# seedrum_triac_v1.net
KiCad netlist of a schematic drawn in EasyEDA
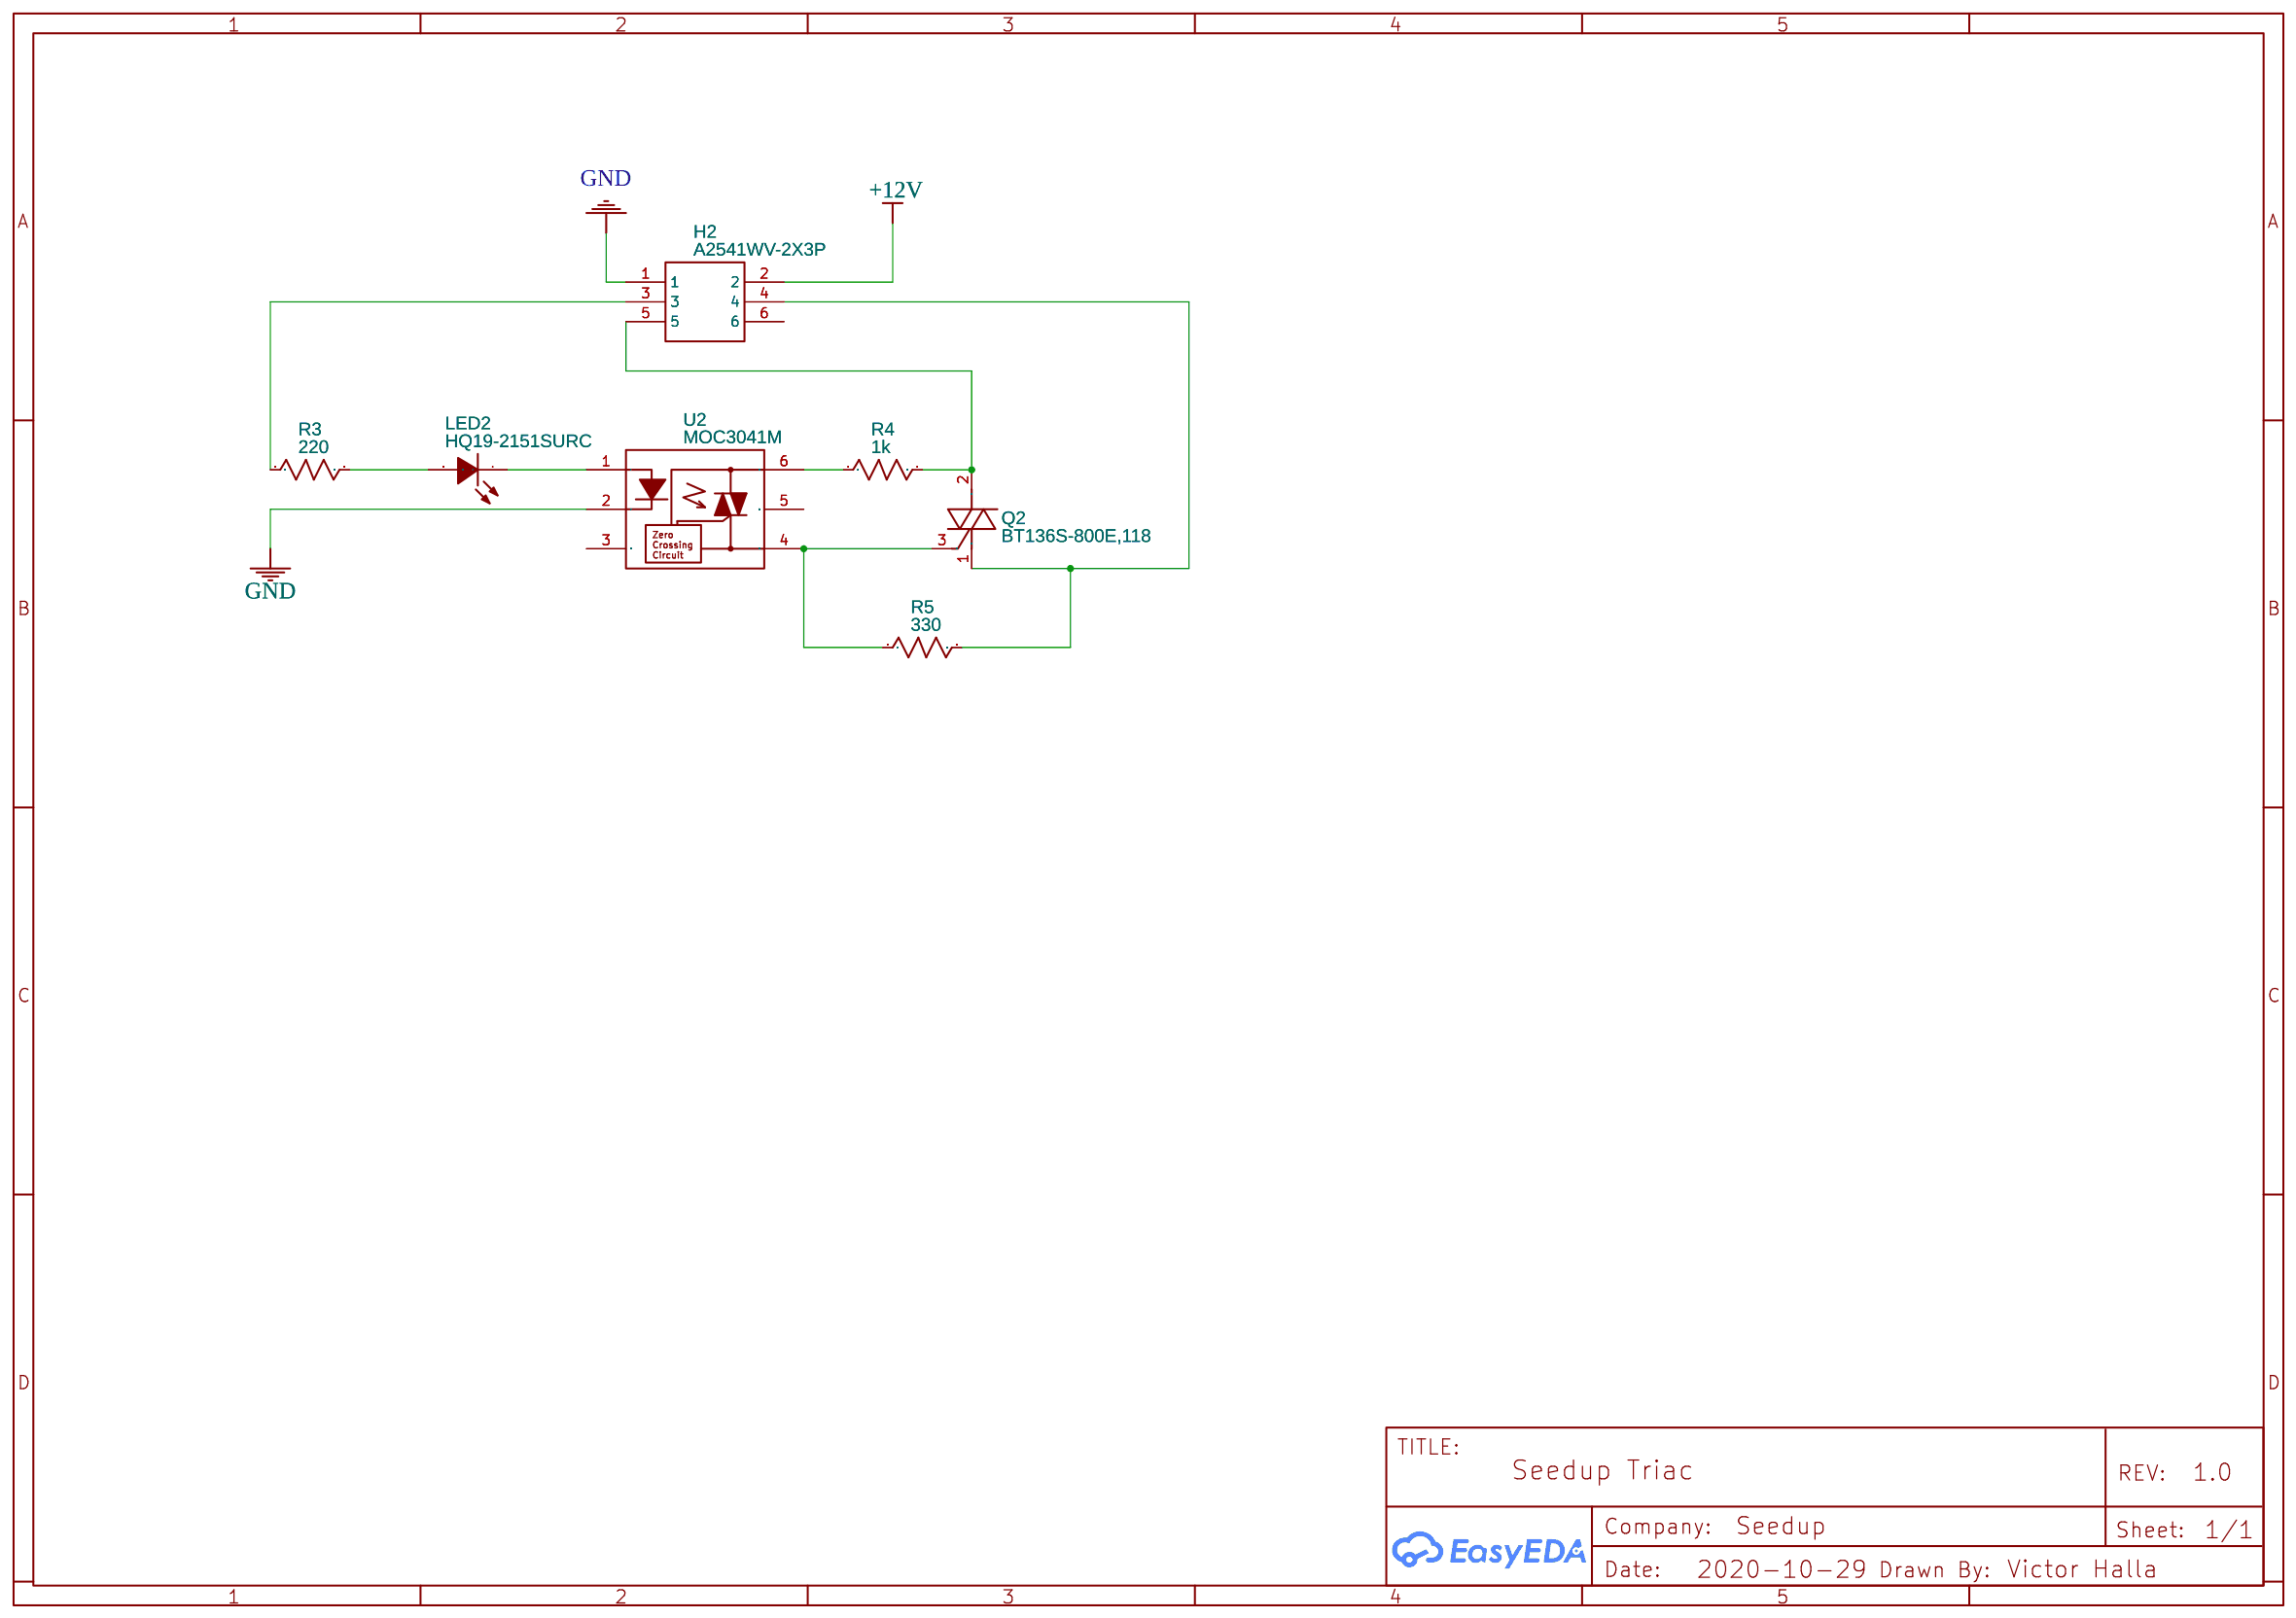
[diagram p0: schematic sheet]

(export (version "E")
  (design (tool "Eeschema 10.0.6"))
  (components
    (comp (ref "H2")
      (value "A2541WV-2X3P")
      (fields
        (field (name "BOM_Manufacturer Part") "A2541WV-2x3P")
        (field (name "BOM_Supplier Part") "C225518")
      )
      (libsource (lib "") (part "A2541WV-2X3P"))
    )
    (comp (ref "LED2")
      (value "HQ19-2151SURC")
      (fields (field (name "BOM_Supplier Part") "C258842"))
      (libsource (lib "") (part "HQ19-2151SURC"))
    )
    (comp (ref "Q2")
      (value "BT136S-800E,118")
      (fields (field (name "BOM_Supplier Part") "C581422"))
      (libsource (lib "") (part "BT136S-800E,118"))
    )
    (comp (ref "R3") (value "220") (libsource (lib "") (part "R_0603_US")))
    (comp (ref "R4") (value "1k") (libsource (lib "") (part "R_0603_US")))
    (comp (ref "R5") (value "330") (libsource (lib "") (part "R_0603_US")))
    (comp (ref "U2")
      (value "MOC3041M")
      (fields (field (name "BOM_Supplier Part") "C8921"))
      (libsource (lib "") (part "MOC3041M"))
    )
  )
  (nets
    (net (code "1") (name "+12V") (class "Default")
      (node (ref "H2") (pin "2") (pinfunction "2_2") (pintype "unspecified"))
    )
    (net (code "2") (name "GND") (class "Default")
      (node (ref "H2") (pin "1") (pinfunction "1_1") (pintype "unspecified"))
      (node (ref "U2") (pin "2") (pinfunction "K_2") (pintype "unspecified"))
    )
    (net (code "3") (name "Net-(H2-Pad3)") (class "Default")
      (node (ref "H2") (pin "3") (pinfunction "3_3") (pintype "unspecified"))
      (node (ref "R3") (pin "1") (pinfunction "1_1") (pintype "unspecified"))
    )
    (net (code "4") (name "Net-(LED2-A)") (class "Default")
      (node (ref "LED2") (pin "2") (pinfunction "A_2") (pintype "unspecified"))
      (node (ref "R3") (pin "2") (pinfunction "2_2") (pintype "unspecified"))
    )
    (net (code "5") (name "Net-(LED2-K)") (class "Default")
      (node (ref "LED2") (pin "1") (pinfunction "K_1") (pintype "unspecified"))
      (node (ref "U2") (pin "1") (pinfunction "A_1") (pintype "unspecified"))
    )
    (net (code "6") (name "Net-(Q2-G)") (class "Default")
      (node (ref "Q2") (pin "3") (pinfunction "G_3") (pintype "unspecified"))
      (node (ref "R5") (pin "1") (pinfunction "1_1") (pintype "unspecified"))
      (node (ref "U2") (pin "4") (pinfunction "T2_4") (pintype "unspecified"))
    )
    (net (code "7") (name "Net-(Q2-T1)") (class "Default")
      (node (ref "H2") (pin "4") (pinfunction "4_4") (pintype "unspecified"))
      (node (ref "Q2") (pin "1") (pinfunction "T1_1") (pintype "unspecified"))
      (node (ref "R5") (pin "2") (pinfunction "2_2") (pintype "unspecified"))
    )
    (net (code "8") (name "Net-(Q2-T2)") (class "Default")
      (node (ref "H2") (pin "5") (pinfunction "5_5") (pintype "unspecified"))
      (node (ref "Q2") (pin "2") (pinfunction "T2_2") (pintype "unspecified"))
      (node (ref "R4") (pin "2") (pinfunction "2_2") (pintype "unspecified"))
    )
    (net (code "9") (name "Net-(U2-T1)") (class "Default")
      (node (ref "R4") (pin "1") (pinfunction "1_1") (pintype "unspecified"))
      (node (ref "U2") (pin "6") (pinfunction "T1_6") (pintype "unspecified"))
    )
    (net (code "10") (name "unconnected-(H2-Pad6)") (class "Default")
      (node (ref "H2") (pin "6") (pinfunction "6_6") (pintype "unspecified"))
    )
    (net (code "11") (name "unconnected-(U2-NC-Pad3)") (class "Default")
      (node (ref "U2") (pin "3") (pinfunction "NC_3") (pintype "unspecified"))
    )
    (net (code "12") (name "unconnected-(U2-NC-Pad5)") (class "Default")
      (node (ref "U2") (pin "5") (pinfunction "NC_5") (pintype "unspecified"))
    )
  )
)
